# Ethernet_Phy_4_esp32.net
KiCad netlist of a schematic drawn in EAGLE
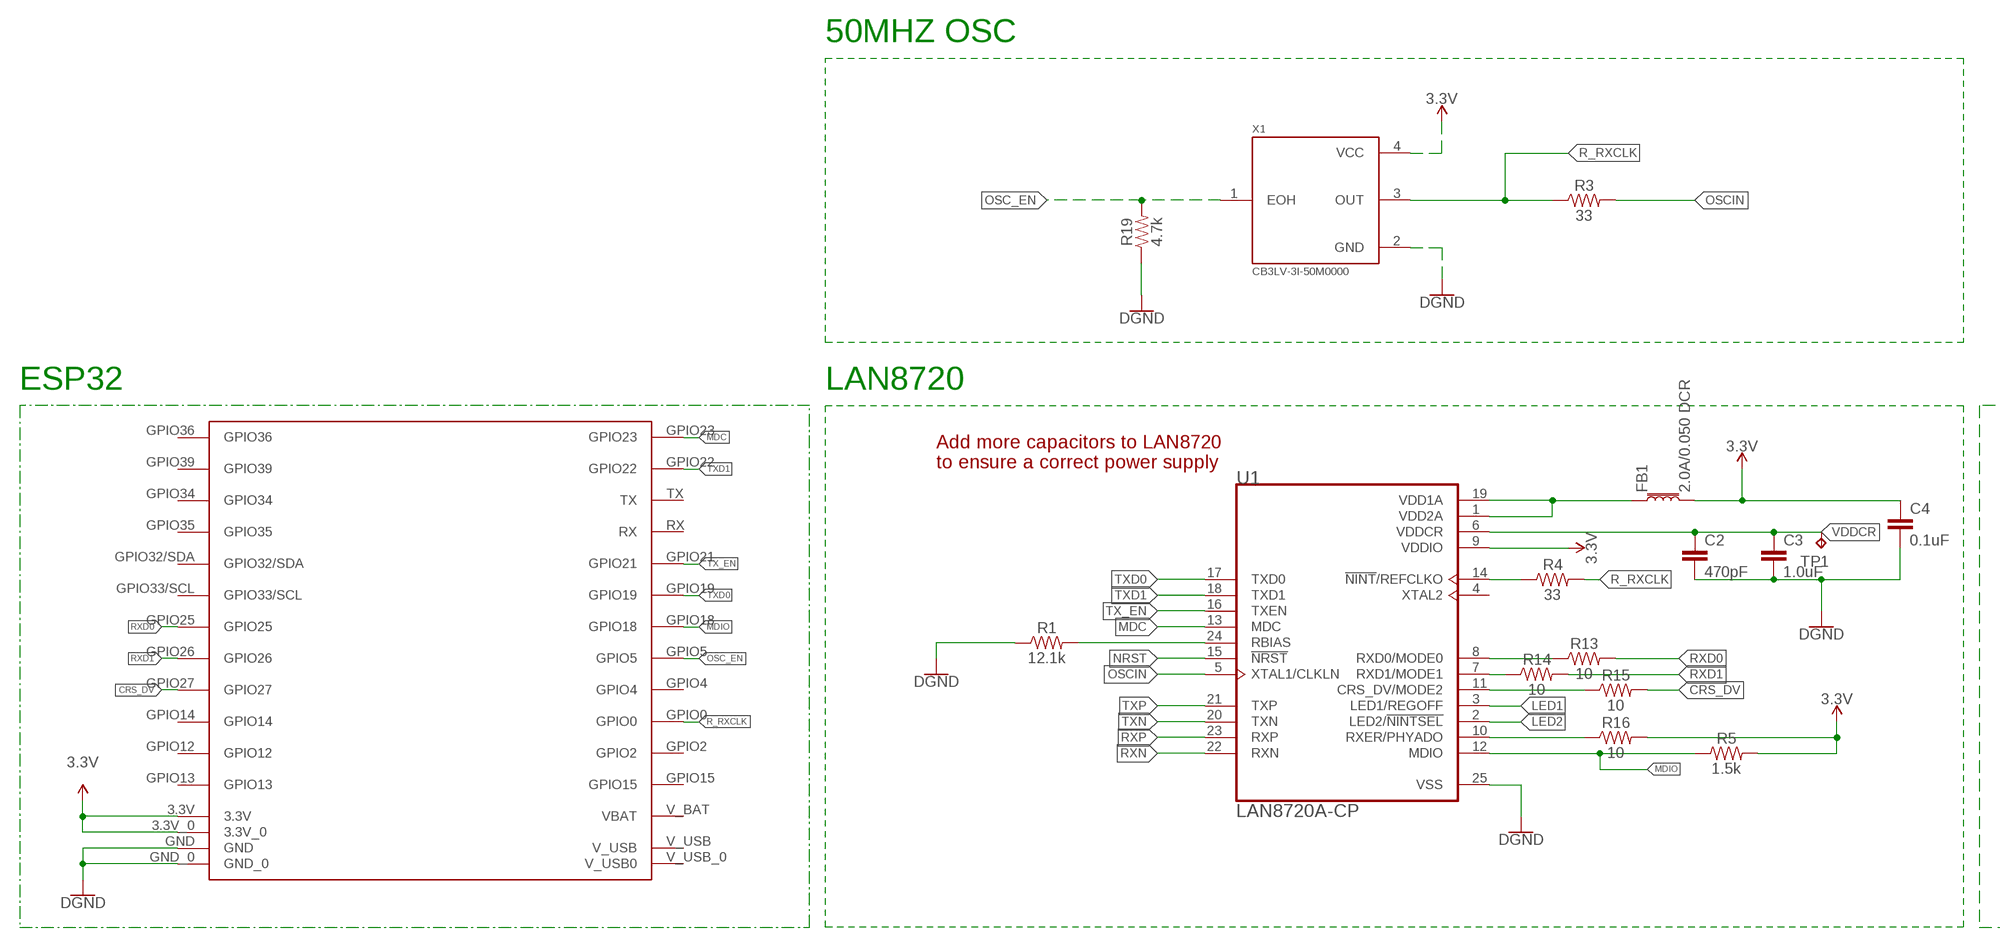
[diagram p0: schematic, sheet 1, part 1 of 2]
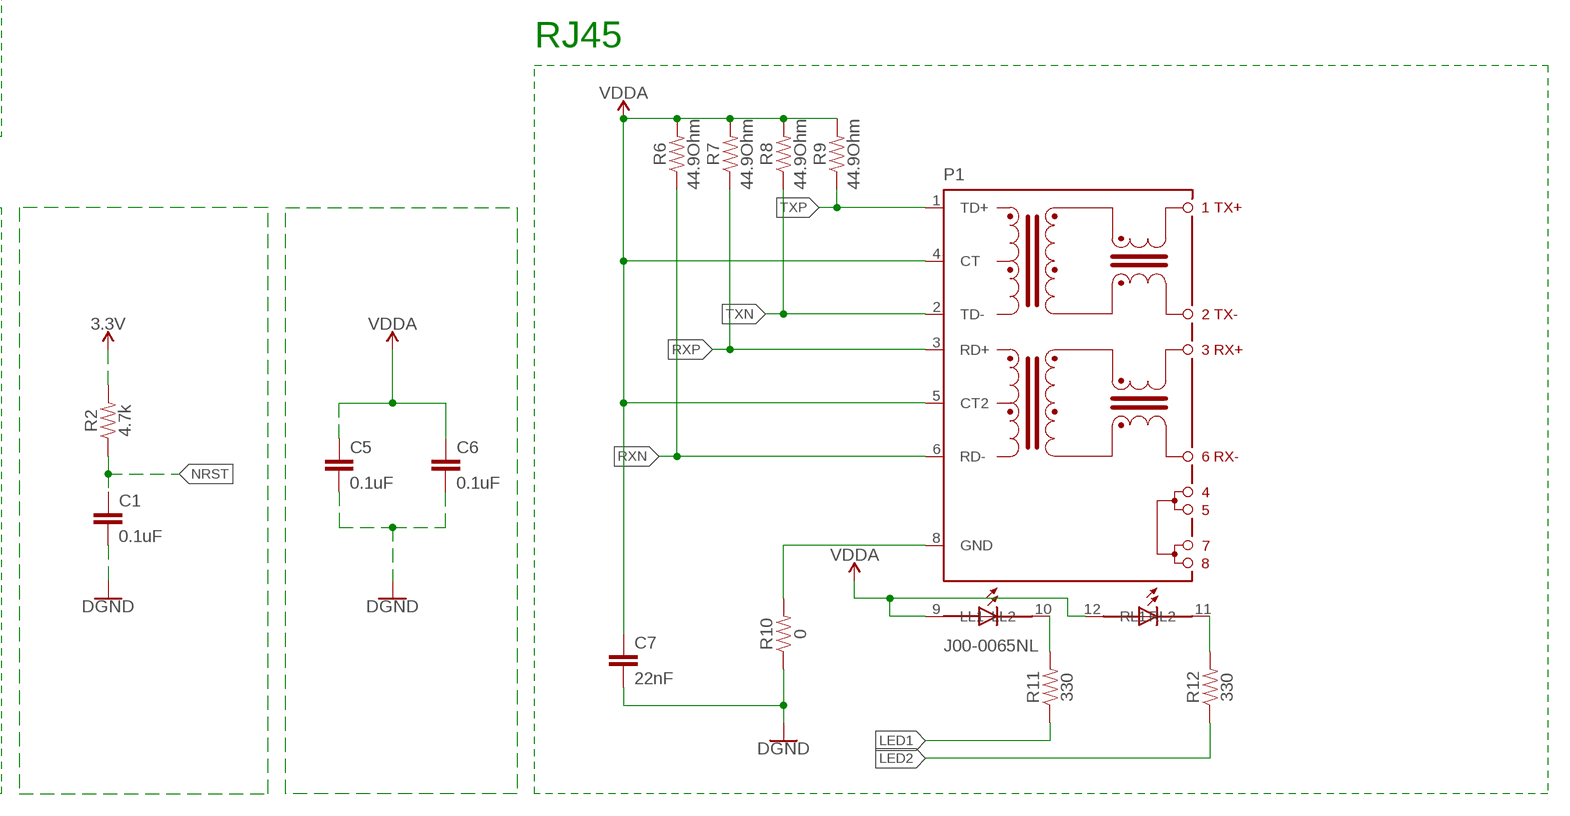
[diagram p1: schematic, sheet 1, part 2 of 2]

(export (version "E")
  (design (tool "Eeschema 10.0.6"))
  (components
    (comp (ref "C1")
      (value "0.1uF")
      (footprint "eagle-import:0603")
      (libsource (lib "eagle-import") (part "0.1UF-0603-100V-10%"))
    )
    (comp (ref "C2")
      (value "470pF")
      (footprint "eagle-import:0603")
      (libsource (lib "eagle-import") (part "470PF-0603-50V-5%"))
    )
    (comp (ref "C3")
      (value "1.0uF")
      (footprint "eagle-import:0603")
      (libsource (lib "eagle-import") (part "1.0UF-0603-16V-10%"))
    )
    (comp (ref "C4")
      (value "0.1uF")
      (footprint "eagle-import:0603")
      (libsource (lib "eagle-import") (part "0.1UF-0603-100V-10%"))
    )
    (comp (ref "C5")
      (value "0.1uF")
      (footprint "eagle-import:0603")
      (libsource (lib "eagle-import") (part "0.1UF-0603-25V-(+80/-20%)"))
    )
    (comp (ref "C6")
      (value "0.1uF")
      (footprint "eagle-import:0603")
      (libsource (lib "eagle-import") (part "0.1UF-0603-25V-(+80/-20%)"))
    )
    (comp (ref "C7")
      (value "22nF")
      (footprint "eagle-import:0603")
      (libsource (lib "eagle-import") (part "22NF/22,000PF-0603-50V-10%"))
    )
    (comp (ref "FB1")
      (value "2.0A/0.050 DCR")
      (footprint "eagle-import:0603")
      (libsource (lib "eagle-import") (part "FERRITE_BEAD-0603"))
    )
    (comp (ref "P1")
      (value "J00-0065NL")
      (footprint "eagle-import:PULSE_J00-0065NL")
      (fields (field (name "MF") "Pulse Electronics"))
      (libsource (lib "eagle-import") (part "J00-0065NL"))
    )
    (comp (ref "R1")
      (value "12.1k")
      (footprint "eagle-import:0603")
      (libsource (lib "eagle-import") (part "12.1KOHM-0603-1/10W-1%"))
    )
    (comp (ref "R2")
      (value "4.7k")
      (footprint "eagle-import:0603")
      (libsource (lib "eagle-import") (part "4.7KOHM-0603-1/10W-1%"))
    )
    (comp (ref "R3")
      (value "33")
      (footprint "eagle-import:0603")
      (libsource (lib "eagle-import") (part "33OHM-0603-1/10W-1%"))
    )
    (comp (ref "R4")
      (value "33")
      (footprint "eagle-import:0603")
      (libsource (lib "eagle-import") (part "33OHM-0603-1/10W-1%"))
    )
    (comp (ref "R5")
      (value "1.5k")
      (footprint "eagle-import:0603")
      (libsource (lib "eagle-import") (part "1.5KOHM-0603-1/10W-1%"))
    )
    (comp (ref "R6")
      (value "44.9Ohm")
      (footprint "eagle-import:0603")
      (libsource (lib "eagle-import") (part "43KOHM-0603-1/10W-1%"))
    )
    (comp (ref "R7")
      (value "44.9Ohm")
      (footprint "eagle-import:0603")
      (libsource (lib "eagle-import") (part "43KOHM-0603-1/10W-1%"))
    )
    (comp (ref "R8")
      (value "44.9Ohm")
      (footprint "eagle-import:0603")
      (libsource (lib "eagle-import") (part "43KOHM-0603-1/10W-1%"))
    )
    (comp (ref "R9")
      (value "44.9Ohm")
      (footprint "eagle-import:0603")
      (libsource (lib "eagle-import") (part "43KOHM-0603-1/10W-1%"))
    )
    (comp (ref "R10")
      (value "0")
      (footprint "eagle-import:0603")
      (libsource (lib "eagle-import") (part "0OHM-0603-1/10W-5%"))
    )
    (comp (ref "R11")
      (value "330")
      (footprint "eagle-import:0603")
      (libsource (lib "eagle-import") (part "330OHM-0603-1/10W-1%"))
    )
    (comp (ref "R12")
      (value "330")
      (footprint "eagle-import:0603")
      (libsource (lib "eagle-import") (part "330OHM-0603-1/10W-1%"))
    )
    (comp (ref "R13")
      (value "10")
      (footprint "eagle-import:0603")
      (libsource (lib "eagle-import") (part "10OHM-0603-1/10W-1%"))
    )
    (comp (ref "R14")
      (value "10")
      (footprint "eagle-import:0603")
      (libsource (lib "eagle-import") (part "10OHM-0603-1/10W-1%"))
    )
    (comp (ref "R15")
      (value "10")
      (footprint "eagle-import:0603")
      (libsource (lib "eagle-import") (part "10OHM-0603-1/10W-1%"))
    )
    (comp (ref "R16")
      (value "10")
      (footprint "eagle-import:0603")
      (libsource (lib "eagle-import") (part "10OHM-0603-1/10W-1%"))
    )
    (comp (ref "R19")
      (value "4.7k")
      (footprint "eagle-import:0603")
      (libsource (lib "eagle-import") (part "4.7KOHM-0603-1/10W-1%"))
    )
    (comp (ref "TP1")
      (value "TPB1,27")
      (footprint "eagle-import:B1,27")
      (libsource (lib "eagle-import") (part "TPB1,27"))
    )
    (comp (ref "U$4")
      (value "OSIBOARD")
      (footprint "eagle-import:OSIBOARD")
      (libsource (lib "eagle-import") (part "OSIBOARD"))
    )
    (comp (ref "U1")
      (value "LAN8720A-CP")
      (footprint "eagle-import:QFN50P400X400X100-25N")
      (fields (field (name "MF") "Microchip"))
      (libsource (lib "eagle-import") (part "LAN8720A-CP"))
    )
    (comp (ref "X1")
      (value "CB3LV-3I-50M0000")
      (footprint "eagle-import:OSCCC700X500X180-4N")
      (fields (field (name "MF") "CTS-Frequency"))
      (libsource (lib "eagle-import") (part "CB3LV-3I-50M0000"))
    )
  )
  (nets
    (net (code "1") (name "3.3V") (class "Default")
      (node (ref "C4") (pin "1") (pinfunction "1_1") (pintype "passive"))
      (node (ref "FB1") (pin "2") (pinfunction "2_2") (pintype "passive"))
      (node (ref "R16") (pin "2") (pinfunction "2_2") (pintype "passive"))
      (node (ref "R2") (pin "2") (pinfunction "2_2") (pintype "passive"))
      (node (ref "R5") (pin "2") (pinfunction "2_2") (pintype "passive"))
      (node (ref "U$4") (pin "3.3V") (pinfunction "3.3V_3.3V") (pintype "bidirectional"))
      (node (ref "U$4") (pin "3.3V_0") (pinfunction "3.3V_0_3.3V_0") (pintype "bidirectional"))
      (node (ref "U1") (pin "9") (pinfunction "VDDIO_9") (pintype "power_in"))
      (node (ref "X1") (pin "4") (pinfunction "VCC_4") (pintype "power_in"))
    )
    (net (code "2") (name "CRS_DV") (class "Default")
      (node (ref "R15") (pin "2") (pinfunction "2_2") (pintype "passive"))
      (node (ref "U$4") (pin "GPIO27") (pinfunction "GPIO27_GPIO27") (pintype "bidirectional"))
    )
    (net (code "3") (name "DGND") (class "Default")
      (node (ref "C1") (pin "2") (pinfunction "2_2") (pintype "passive"))
      (node (ref "C2") (pin "2") (pinfunction "2_2") (pintype "passive"))
      (node (ref "C3") (pin "2") (pinfunction "2_2") (pintype "passive"))
      (node (ref "C4") (pin "2") (pinfunction "2_2") (pintype "passive"))
      (node (ref "C5") (pin "2") (pinfunction "2_2") (pintype "passive"))
      (node (ref "C6") (pin "2") (pinfunction "2_2") (pintype "passive"))
      (node (ref "C7") (pin "2") (pinfunction "2_2") (pintype "passive"))
      (node (ref "R1") (pin "1") (pinfunction "1_1") (pintype "passive"))
      (node (ref "R10") (pin "1") (pinfunction "1_1") (pintype "passive"))
      (node (ref "R19") (pin "1") (pinfunction "1_1") (pintype "passive"))
      (node (ref "U$4") (pin "GND") (pinfunction "GND_GND") (pintype "bidirectional"))
      (node (ref "U$4") (pin "GND_0") (pinfunction "GND_0_GND_0") (pintype "bidirectional"))
      (node (ref "U1") (pin "25") (pinfunction "VSS_25") (pintype "power_in"))
      (node (ref "X1") (pin "2") (pinfunction "GND_2") (pintype "passive"))
    )
    (net (code "4") (name "LED1") (class "Default")
      (node (ref "R11") (pin "1") (pinfunction "1_1") (pintype "passive"))
      (node (ref "U1") (pin "3") (pinfunction "LED1/REGOFF_3") (pintype "bidirectional"))
    )
    (net (code "5") (name "LED2") (class "Default")
      (node (ref "R12") (pin "1") (pinfunction "1_1") (pintype "passive"))
      (node (ref "U1") (pin "2") (pinfunction "LED2/~{NINTSEL}_2") (pintype "bidirectional"))
    )
    (net (code "6") (name "MDC") (class "Default")
      (node (ref "U$4") (pin "GPIO23") (pinfunction "GPIO23_GPIO23") (pintype "bidirectional"))
      (node (ref "U1") (pin "13") (pinfunction "MDC_13") (pintype "input"))
    )
    (net (code "7") (name "MDIO") (class "Default")
      (node (ref "R5") (pin "1") (pinfunction "1_1") (pintype "passive"))
      (node (ref "U$4") (pin "GPIO18") (pinfunction "GPIO18_GPIO18") (pintype "bidirectional"))
      (node (ref "U1") (pin "12") (pinfunction "MDIO_12") (pintype "bidirectional"))
    )
    (net (code "8") (name "NRST") (class "Default")
      (node (ref "C1") (pin "1") (pinfunction "1_1") (pintype "passive"))
      (node (ref "R2") (pin "1") (pinfunction "1_1") (pintype "passive"))
      (node (ref "U1") (pin "15") (pinfunction "~{NRST}_15") (pintype "input"))
    )
    (net (code "9") (name "Net-(P1-GND)") (class "Default")
      (node (ref "P1") (pin "8") (pinfunction "GND_8") (pintype "passive"))
      (node (ref "R10") (pin "2") (pinfunction "2_2") (pintype "passive"))
    )
    (net (code "10") (name "Net-(P1-LL2)") (class "Default")
      (node (ref "P1") (pin "10") (pinfunction "LL2_10") (pintype "passive"))
      (node (ref "R11") (pin "2") (pinfunction "2_2") (pintype "passive"))
    )
    (net (code "11") (name "Net-(P1-RL2)") (class "Default")
      (node (ref "P1") (pin "11") (pinfunction "RL2_11") (pintype "passive"))
      (node (ref "R12") (pin "2") (pinfunction "2_2") (pintype "passive"))
    )
    (net (code "12") (name "Net-(U1-CRS_DV{slash}MODE2)") (class "Default")
      (node (ref "R15") (pin "1") (pinfunction "1_1") (pintype "passive"))
      (node (ref "U1") (pin "11") (pinfunction "CRS_DV/MODE2_11") (pintype "bidirectional"))
    )
    (net (code "13") (name "Net-(U1-RBIAS)") (class "Default")
      (node (ref "R1") (pin "2") (pinfunction "2_2") (pintype "passive"))
      (node (ref "U1") (pin "24") (pinfunction "RBIAS_24") (pintype "input"))
    )
    (net (code "14") (name "Net-(U1-RXD0{slash}MODE0)") (class "Default")
      (node (ref "R13") (pin "1") (pinfunction "1_1") (pintype "passive"))
      (node (ref "U1") (pin "8") (pinfunction "RXD0/MODE0_8") (pintype "bidirectional"))
    )
    (net (code "15") (name "Net-(U1-RXD1{slash}MODE1)") (class "Default")
      (node (ref "R14") (pin "1") (pinfunction "1_1") (pintype "passive"))
      (node (ref "U1") (pin "7") (pinfunction "RXD1/MODE1_7") (pintype "bidirectional"))
    )
    (net (code "16") (name "Net-(U1-RXER{slash}PHYADO)") (class "Default")
      (node (ref "R16") (pin "1") (pinfunction "1_1") (pintype "passive"))
      (node (ref "U1") (pin "10") (pinfunction "RXER/PHYADO_10") (pintype "bidirectional"))
    )
    (net (code "17") (name "Net-(U1-VDD1A)") (class "Default")
      (node (ref "FB1") (pin "1") (pinfunction "1_1") (pintype "passive"))
      (node (ref "U1") (pin "1") (pinfunction "VDD2A_1") (pintype "power_in"))
      (node (ref "U1") (pin "19") (pinfunction "VDD1A_19") (pintype "power_in"))
    )
    (net (code "18") (name "Net-(U1-~{NINT}{slash}REFCLKO)") (class "Default")
      (node (ref "R4") (pin "1") (pinfunction "1_1") (pintype "passive"))
      (node (ref "U1") (pin "14") (pinfunction "~{NINT}/REFCLKO_14") (pintype "output"))
    )
    (net (code "19") (name "OSCIN") (class "Default")
      (node (ref "R3") (pin "2") (pinfunction "2_2") (pintype "passive"))
      (node (ref "U1") (pin "5") (pinfunction "XTAL1/CLKLN_5") (pintype "input"))
    )
    (net (code "20") (name "OSC_EN") (class "Default")
      (node (ref "R19") (pin "2") (pinfunction "2_2") (pintype "passive"))
      (node (ref "U$4") (pin "GPIO5") (pinfunction "GPIO5_GPIO5") (pintype "bidirectional"))
      (node (ref "X1") (pin "1") (pinfunction "EOH_1") (pintype "input"))
    )
    (net (code "21") (name "RXD0") (class "Default")
      (node (ref "R13") (pin "2") (pinfunction "2_2") (pintype "passive"))
      (node (ref "U$4") (pin "GPIO25") (pinfunction "GPIO25_GPIO25") (pintype "bidirectional"))
    )
    (net (code "22") (name "RXD1") (class "Default")
      (node (ref "R14") (pin "2") (pinfunction "2_2") (pintype "passive"))
      (node (ref "U$4") (pin "GPIO26") (pinfunction "GPIO26_GPIO26") (pintype "bidirectional"))
    )
    (net (code "23") (name "RXN") (class "Default")
      (node (ref "P1") (pin "6") (pinfunction "RD-_6") (pintype "input"))
      (node (ref "R6") (pin "1") (pinfunction "1_1") (pintype "passive"))
      (node (ref "U1") (pin "22") (pinfunction "RXN_22") (pintype "bidirectional"))
    )
    (net (code "24") (name "RXP") (class "Default")
      (node (ref "P1") (pin "3") (pinfunction "RD+_3") (pintype "input"))
      (node (ref "R7") (pin "1") (pinfunction "1_1") (pintype "passive"))
      (node (ref "U1") (pin "23") (pinfunction "RXP_23") (pintype "bidirectional"))
    )
    (net (code "25") (name "R_RXCLK") (class "Default")
      (node (ref "R3") (pin "1") (pinfunction "1_1") (pintype "passive"))
      (node (ref "R4") (pin "2") (pinfunction "2_2") (pintype "passive"))
      (node (ref "U$4") (pin "GPIO0") (pinfunction "GPIO0_GPIO0") (pintype "bidirectional"))
      (node (ref "X1") (pin "3") (pinfunction "OUT_3") (pintype "output"))
    )
    (net (code "26") (name "TXD0") (class "Default")
      (node (ref "U$4") (pin "GPIO19") (pinfunction "GPIO19_GPIO19") (pintype "bidirectional"))
      (node (ref "U1") (pin "17") (pinfunction "TXD0_17") (pintype "input"))
    )
    (net (code "27") (name "TXD1") (class "Default")
      (node (ref "U$4") (pin "GPIO22") (pinfunction "GPIO22_GPIO22") (pintype "bidirectional"))
      (node (ref "U1") (pin "18") (pinfunction "TXD1_18") (pintype "input"))
    )
    (net (code "28") (name "TXN") (class "Default")
      (node (ref "P1") (pin "2") (pinfunction "TD-_2") (pintype "input"))
      (node (ref "R8") (pin "1") (pinfunction "1_1") (pintype "passive"))
      (node (ref "U1") (pin "20") (pinfunction "TXN_20") (pintype "bidirectional"))
    )
    (net (code "29") (name "TXP") (class "Default")
      (node (ref "P1") (pin "1") (pinfunction "TD+_1") (pintype "input"))
      (node (ref "R9") (pin "1") (pinfunction "1_1") (pintype "passive"))
      (node (ref "U1") (pin "21") (pinfunction "TXP_21") (pintype "bidirectional"))
    )
    (net (code "30") (name "TX_EN") (class "Default")
      (node (ref "U$4") (pin "GPIO21") (pinfunction "GPIO21_GPIO21") (pintype "bidirectional"))
      (node (ref "U1") (pin "16") (pinfunction "TXEN_16") (pintype "input"))
    )
    (net (code "31") (name "VDDA") (class "Default")
      (node (ref "C5") (pin "1") (pinfunction "1_1") (pintype "passive"))
      (node (ref "C6") (pin "1") (pinfunction "1_1") (pintype "passive"))
      (node (ref "C7") (pin "1") (pinfunction "1_1") (pintype "passive"))
      (node (ref "P1") (pin "12") (pinfunction "RL1_12") (pintype "passive"))
      (node (ref "P1") (pin "4") (pinfunction "CT_4") (pintype "input"))
      (node (ref "P1") (pin "5") (pinfunction "CT2_5") (pintype "input"))
      (node (ref "P1") (pin "9") (pinfunction "LL1_9") (pintype "passive"))
      (node (ref "R6") (pin "2") (pinfunction "2_2") (pintype "passive"))
      (node (ref "R7") (pin "2") (pinfunction "2_2") (pintype "passive"))
      (node (ref "R8") (pin "2") (pinfunction "2_2") (pintype "passive"))
      (node (ref "R9") (pin "2") (pinfunction "2_2") (pintype "passive"))
    )
    (net (code "32") (name "VDDCR") (class "Default")
      (node (ref "C2") (pin "1") (pinfunction "1_1") (pintype "passive"))
      (node (ref "C3") (pin "1") (pinfunction "1_1") (pintype "passive"))
      (node (ref "TP1") (pin "TP") (pinfunction "TP_TP") (pintype "input"))
      (node (ref "U1") (pin "6") (pinfunction "VDDCR_6") (pintype "power_in"))
    )
    (net (code "33") (name "unconnected-(U$4-PadGPIO2)") (class "Default")
      (node (ref "U$4") (pin "GPIO2") (pinfunction "GPIO2_GPIO2") (pintype "bidirectional"))
    )
    (net (code "34") (name "unconnected-(U$4-PadGPIO4)") (class "Default")
      (node (ref "U$4") (pin "GPIO4") (pinfunction "GPIO4_GPIO4") (pintype "bidirectional"))
    )
    (net (code "35") (name "unconnected-(U$4-PadGPIO12)") (class "Default")
      (node (ref "U$4") (pin "GPIO12") (pinfunction "GPIO12_GPIO12") (pintype "bidirectional"))
    )
    (net (code "36") (name "unconnected-(U$4-PadGPIO13)") (class "Default")
      (node (ref "U$4") (pin "GPIO13") (pinfunction "GPIO13_GPIO13") (pintype "bidirectional"))
    )
    (net (code "37") (name "unconnected-(U$4-PadGPIO14)") (class "Default")
      (node (ref "U$4") (pin "GPIO14") (pinfunction "GPIO14_GPIO14") (pintype "bidirectional"))
    )
    (net (code "38") (name "unconnected-(U$4-PadGPIO15)") (class "Default")
      (node (ref "U$4") (pin "GPIO15") (pinfunction "GPIO15_GPIO15") (pintype "bidirectional"))
    )
    (net (code "39") (name "unconnected-(U$4-PadGPIO32{slash}SDA)") (class "Default")
      (node (ref "U$4") (pin "GPIO32/SDA") (pinfunction "GPIO32/SDA_GPIO32/SDA") (pintype "bidirectional"))
    )
    (net (code "40") (name "unconnected-(U$4-PadGPIO33{slash}SCL)") (class "Default")
      (node (ref "U$4") (pin "GPIO33/SCL") (pinfunction "GPIO33/SCL_GPIO33/SCL") (pintype "bidirectional"))
    )
    (net (code "41") (name "unconnected-(U$4-PadGPIO34)") (class "Default")
      (node (ref "U$4") (pin "GPIO34") (pinfunction "GPIO34_GPIO34") (pintype "bidirectional"))
    )
    (net (code "42") (name "unconnected-(U$4-PadGPIO35)") (class "Default")
      (node (ref "U$4") (pin "GPIO35") (pinfunction "GPIO35_GPIO35") (pintype "bidirectional"))
    )
    (net (code "43") (name "unconnected-(U$4-PadGPIO36)") (class "Default")
      (node (ref "U$4") (pin "GPIO36") (pinfunction "GPIO36_GPIO36") (pintype "bidirectional"))
    )
    (net (code "44") (name "unconnected-(U$4-PadGPIO39)") (class "Default")
      (node (ref "U$4") (pin "GPIO39") (pinfunction "GPIO39_GPIO39") (pintype "bidirectional"))
    )
    (net (code "45") (name "unconnected-(U$4-PadRX)") (class "Default")
      (node (ref "U$4") (pin "RX") (pinfunction "RX_RX") (pintype "bidirectional"))
    )
    (net (code "46") (name "unconnected-(U$4-PadTX)") (class "Default")
      (node (ref "U$4") (pin "TX") (pinfunction "TX_TX") (pintype "bidirectional"))
    )
    (net (code "47") (name "unconnected-(U$4-PadV_USB)") (class "Default")
      (node (ref "U$4") (pin "V_USB") (pinfunction "V_USB_V_USB") (pintype "bidirectional"))
    )
    (net (code "48") (name "unconnected-(U$4-VBAT-PadV_BAT)") (class "Default")
      (node (ref "U$4") (pin "V_BAT") (pinfunction "VBAT_V_BAT") (pintype "bidirectional"))
    )
    (net (code "49") (name "unconnected-(U$4-V_USB0-PadV_USB_0)") (class "Default")
      (node (ref "U$4") (pin "V_USB_0") (pinfunction "V_USB0_V_USB_0") (pintype "bidirectional"))
    )
    (net (code "50") (name "unconnected-(U1-XTAL2-Pad4)") (class "Default")
      (node (ref "U1") (pin "4") (pinfunction "XTAL2_4") (pintype "output"))
    )
  )
)
